# CONNECTOR_A.net
KiCad netlist of a schematic drawn in Altium Designer
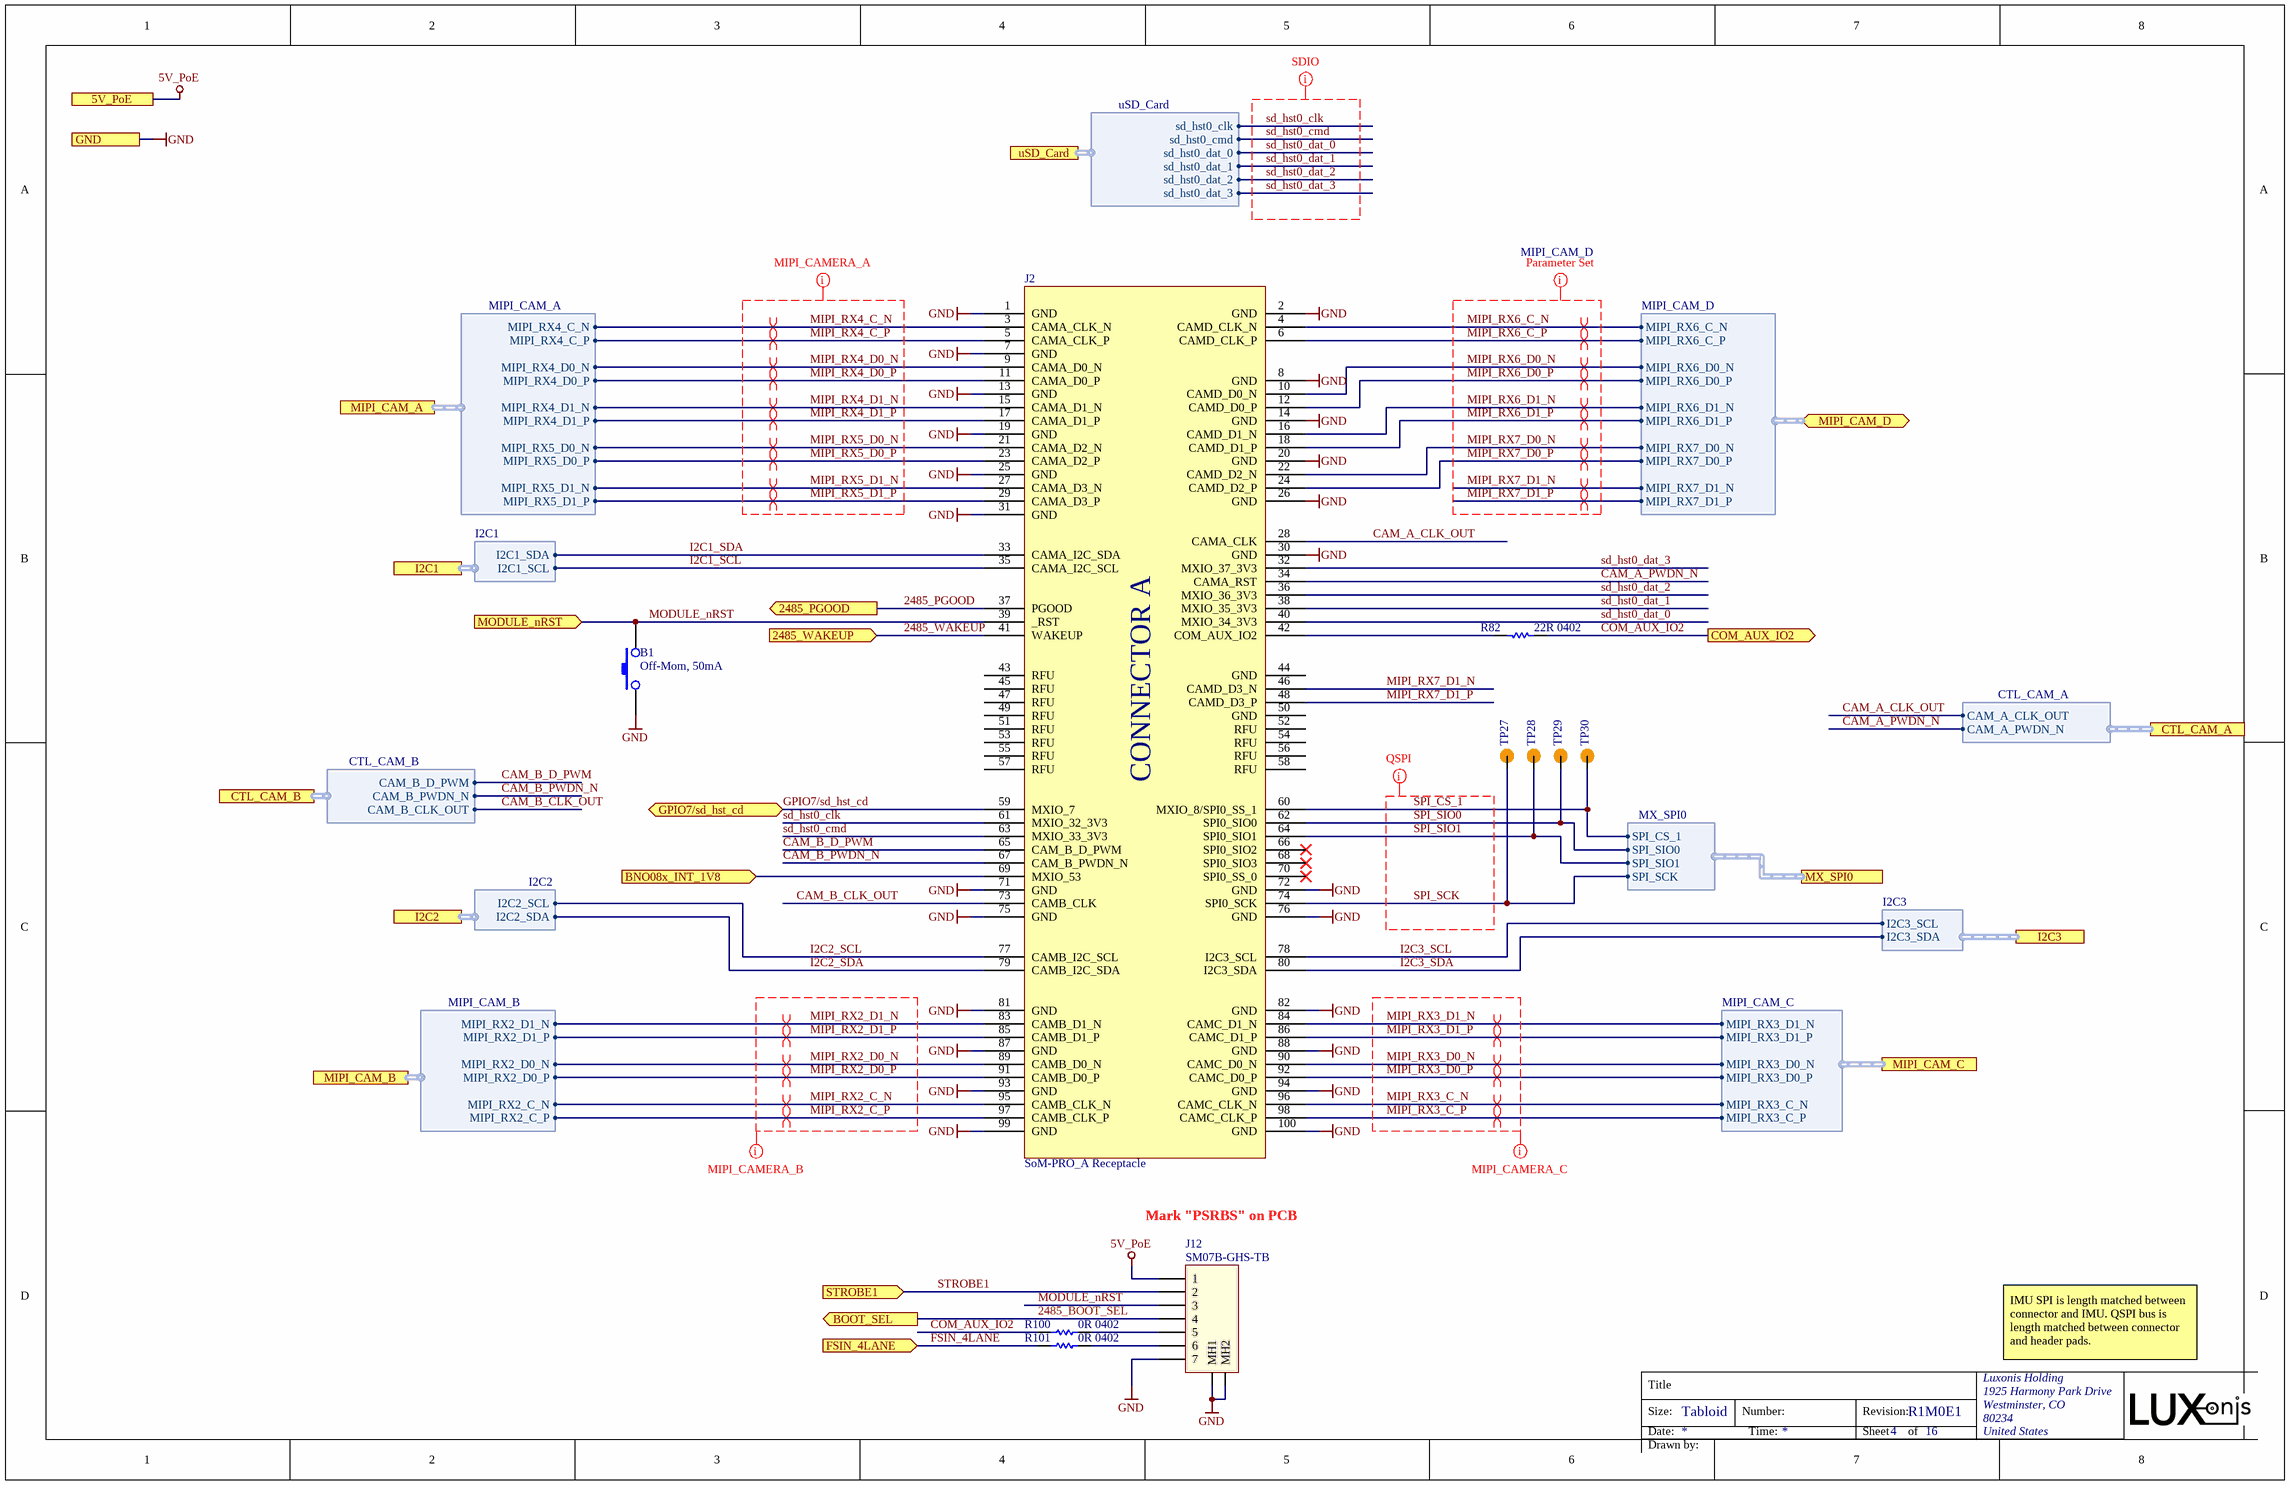
[diagram p0: CONNECTOR_A.SchDoc]

(export (version "E")
  (design (tool "Eeschema 10.0.6"))
  (components
    (comp (ref "B1")
      (value "Off-Mom, 50mA")
      (footprint "LuxonisMaster:DTSM-32N-V")
      (description "SWITCH TACTILE SMT 3.5mm * 6mm , brown 160gf")
      (libsource (lib "LuxonisMaster") (part "DTSM-32N-V"))
    )
    (comp (ref "J2")
      (value "SoM-PRO_A Receptacle")
      (footprint "LuxonisMaster:CON_A_BW2099_SoM_DF40HC-3.0-100DS-0.4V_minpad")
      (description "CONN RCPT 100POS 0.4MM SMD GOLD")
      (libsource (lib "LuxonisMaster") (part "DF40HC(3.0)-100DS-0.4V_SoM-PRO_A"))
    )
    (comp (ref "J12")
      (value "SM07B-GHS-TB")
      (footprint "SM07B-GHS-TB")
      (description "Conn Shrouded Header HDR 7 POS 1.25mm Solder RA Side Entry SMD T/R")
      (libsource (lib "DD2090_4CAM_FFC") (part "SM07B-GHS-TB(LF)(SN)"))
    )
    (comp (ref "R82")
      (value "22R 0402")
      (footprint "RES_Altium_Vault_Generic:RESC0402(1005)_L")
      (description "RES SMD 22 OHM 1% 1/16W 0402")
      (fields (field (name "TOLERANCE") "1%"))
      (libsource (lib "BW2098POE") (part "RC0402FR-0722RL"))
    )
    (comp (ref "R100")
      (value "0R 0402")
      (footprint "RES_Altium_Vault_Generic:RESC0402(1005)_L")
      (description "RES SMD 0 OHM JUMPER 1/16W 0402")
      (fields (field (name "TOLERANCE") "5%"))
      (libsource (lib "LuxonisMaster") (part "CRCW04020000Z0ED"))
    )
    (comp (ref "R101")
      (value "0R 0402")
      (footprint "RES_Altium_Vault_Generic:RESC0402(1005)_L")
      (description "RES SMD 0 OHM JUMPER 1/16W 0402")
      (fields (field (name "TOLERANCE") "5%"))
      (libsource (lib "LuxonisMaster") (part "CRCW04020000Z0ED"))
    )
    (comp (ref "TP27")
      (value "TP100_200_NS")
      (footprint "TP100_200_NS")
      (libsource (lib "LuxonisMaster") (part "TEST_POINT"))
    )
    (comp (ref "TP28")
      (value "TP100_200_NS")
      (footprint "TP100_200_NS")
      (libsource (lib "LuxonisMaster") (part "TEST_POINT"))
    )
    (comp (ref "TP29")
      (value "TP100_200_NS")
      (footprint "TP100_200_NS")
      (libsource (lib "LuxonisMaster") (part "TEST_POINT"))
    )
    (comp (ref "TP30")
      (value "TP100_200_NS")
      (footprint "TP100_200_NS")
      (libsource (lib "LuxonisMaster") (part "TEST_POINT"))
    )
  )
  (nets
    (net (code "12") (name "/2485_BOOT_SEL") (class "Default")
      (node (ref "J12") (pin "4") (pinfunction "4_4") (pintype "passive"))
    )
    (net (code "13") (name "/2485_PGOOD") (class "Default")
      (node (ref "J2") (pin "37") (pinfunction "PGOOD_37") (pintype "passive"))
    )
    (net (code "14") (name "/2485_WAKEUP") (class "Default")
      (node (ref "J2") (pin "41") (pinfunction "WAKEUP_41") (pintype "passive"))
    )
    (net (code "15") (name "/BNO08x_INT_1V8") (class "Default")
      (node (ref "J2") (pin "69") (pinfunction "MXIO_53_69") (pintype "passive"))
    )
    (net (code "16") (name "/CAM_A_CLK_OUT") (class "Default")
      (node (ref "J2") (pin "28") (pinfunction "CAMA_CLK_28") (pintype "passive"))
    )
    (net (code "17") (name "/CAM_A_PWDN_N") (class "Default")
      (node (ref "J2") (pin "34") (pinfunction "CAMA_RST_34") (pintype "passive"))
    )
    (net (code "18") (name "/CAM_B_CLK_OUT") (class "Default")
      (node (ref "J2") (pin "73") (pinfunction "CAMB_CLK_73") (pintype "passive"))
    )
    (net (code "19") (name "/CAM_B_D_PWM") (class "Default")
      (node (ref "J2") (pin "65") (pinfunction "CAM_B_D_PWM_65") (pintype "passive"))
    )
    (net (code "20") (name "/CAM_B_PWDN_N") (class "Default")
      (node (ref "J2") (pin "67") (pinfunction "CAM_B_PWDN_N_67") (pintype "passive"))
    )
    (net (code "21") (name "/COM_AUX_IO2") (class "Default")
      (node (ref "R100") (pin "1") (pinfunction "1_1") (pintype "passive"))
      (node (ref "R82") (pin "1") (pinfunction "1_1") (pintype "passive"))
    )
    (net (code "22") (name "/FSIN_4LANE") (class "Default")
      (node (ref "R101") (pin "1") (pinfunction "1_1") (pintype "passive"))
    )
    (net (code "23") (name "/GPIO7{slash}sd_hst_cd") (class "Default")
      (node (ref "J2") (pin "59") (pinfunction "MXIO_7_59") (pintype "passive"))
    )
    (net (code "24") (name "/I2C1_SCL") (class "Default")
      (node (ref "J2") (pin "35") (pinfunction "CAMA_I2C_SCL_35") (pintype "passive"))
    )
    (net (code "25") (name "/I2C1_SDA") (class "Default")
      (node (ref "J2") (pin "33") (pinfunction "CAMA_I2C_SDA_33") (pintype "passive"))
    )
    (net (code "26") (name "/I2C2_SCL") (class "Default")
      (node (ref "J2") (pin "77") (pinfunction "CAMB_I2C_SCL_77") (pintype "passive"))
    )
    (net (code "27") (name "/I2C2_SDA") (class "Default")
      (node (ref "J2") (pin "79") (pinfunction "CAMB_I2C_SDA_79") (pintype "passive"))
    )
    (net (code "28") (name "/I2C3_SCL") (class "Default")
      (node (ref "J2") (pin "78") (pinfunction "I2C3_SCL_78") (pintype "passive"))
    )
    (net (code "29") (name "/I2C3_SDA") (class "Default")
      (node (ref "J2") (pin "80") (pinfunction "I2C3_SDA_80") (pintype "passive"))
    )
    (net (code "30") (name "/MIPI_RX2_C_N") (class "Default")
      (node (ref "J2") (pin "95") (pinfunction "CAMB_CLK_N_95") (pintype "passive"))
    )
    (net (code "31") (name "/MIPI_RX2_C_P") (class "Default")
      (node (ref "J2") (pin "97") (pinfunction "CAMB_CLK_P_97") (pintype "passive"))
    )
    (net (code "32") (name "/MIPI_RX2_D0_N") (class "Default")
      (node (ref "J2") (pin "89") (pinfunction "CAMB_D0_N_89") (pintype "passive"))
    )
    (net (code "33") (name "/MIPI_RX2_D0_P") (class "Default")
      (node (ref "J2") (pin "91") (pinfunction "CAMB_D0_P_91") (pintype "passive"))
    )
    (net (code "34") (name "/MIPI_RX2_D1_N") (class "Default")
      (node (ref "J2") (pin "83") (pinfunction "CAMB_D1_N_83") (pintype "passive"))
    )
    (net (code "35") (name "/MIPI_RX2_D1_P") (class "Default")
      (node (ref "J2") (pin "85") (pinfunction "CAMB_D1_P_85") (pintype "passive"))
    )
    (net (code "36") (name "/MIPI_RX3_C_N") (class "Default")
      (node (ref "J2") (pin "96") (pinfunction "CAMC_CLK_N_96") (pintype "passive"))
    )
    (net (code "37") (name "/MIPI_RX3_C_P") (class "Default")
      (node (ref "J2") (pin "98") (pinfunction "CAMC_CLK_P_98") (pintype "passive"))
    )
    (net (code "38") (name "/MIPI_RX3_D0_N") (class "Default")
      (node (ref "J2") (pin "90") (pinfunction "CAMC_D0_N_90") (pintype "passive"))
    )
    (net (code "39") (name "/MIPI_RX3_D0_P") (class "Default")
      (node (ref "J2") (pin "92") (pinfunction "CAMC_D0_P_92") (pintype "passive"))
    )
    (net (code "40") (name "/MIPI_RX3_D1_N") (class "Default")
      (node (ref "J2") (pin "84") (pinfunction "CAMC_D1_N_84") (pintype "passive"))
    )
    (net (code "41") (name "/MIPI_RX3_D1_P") (class "Default")
      (node (ref "J2") (pin "86") (pinfunction "CAMC_D1_P_86") (pintype "passive"))
    )
    (net (code "42") (name "/MIPI_RX4_C_N") (class "Default")
      (node (ref "J2") (pin "3") (pinfunction "CAMA_CLK_N_3") (pintype "passive"))
    )
    (net (code "43") (name "/MIPI_RX4_C_P") (class "Default")
      (node (ref "J2") (pin "5") (pinfunction "CAMA_CLK_P_5") (pintype "passive"))
    )
    (net (code "44") (name "/MIPI_RX4_D0_N") (class "Default")
      (node (ref "J2") (pin "9") (pinfunction "CAMA_D0_N_9") (pintype "passive"))
    )
    (net (code "45") (name "/MIPI_RX4_D0_P") (class "Default")
      (node (ref "J2") (pin "11") (pinfunction "CAMA_D0_P_11") (pintype "passive"))
    )
    (net (code "46") (name "/MIPI_RX4_D1_N") (class "Default")
      (node (ref "J2") (pin "15") (pinfunction "CAMA_D1_N_15") (pintype "passive"))
    )
    (net (code "47") (name "/MIPI_RX4_D1_P") (class "Default")
      (node (ref "J2") (pin "17") (pinfunction "CAMA_D1_P_17") (pintype "passive"))
    )
    (net (code "48") (name "/MIPI_RX5_D0_N") (class "Default")
      (node (ref "J2") (pin "21") (pinfunction "CAMA_D2_N_21") (pintype "passive"))
    )
    (net (code "49") (name "/MIPI_RX5_D0_P") (class "Default")
      (node (ref "J2") (pin "23") (pinfunction "CAMA_D2_P_23") (pintype "passive"))
    )
    (net (code "50") (name "/MIPI_RX5_D1_N") (class "Default")
      (node (ref "J2") (pin "27") (pinfunction "CAMA_D3_N_27") (pintype "passive"))
    )
    (net (code "51") (name "/MIPI_RX5_D1_P") (class "Default")
      (node (ref "J2") (pin "29") (pinfunction "CAMA_D3_P_29") (pintype "passive"))
    )
    (net (code "52") (name "/MIPI_RX6_C_N") (class "Default")
      (node (ref "J2") (pin "4") (pinfunction "CAMD_CLK_N_4") (pintype "passive"))
    )
    (net (code "53") (name "/MIPI_RX6_C_P") (class "Default")
      (node (ref "J2") (pin "6") (pinfunction "CAMD_CLK_P_6") (pintype "passive"))
    )
    (net (code "54") (name "/MIPI_RX6_D0_N") (class "Default")
      (node (ref "J2") (pin "10") (pinfunction "CAMD_D0_N_10") (pintype "passive"))
    )
    (net (code "55") (name "/MIPI_RX6_D0_P") (class "Default")
      (node (ref "J2") (pin "12") (pinfunction "CAMD_D0_P_12") (pintype "passive"))
    )
    (net (code "56") (name "/MIPI_RX6_D1_N") (class "Default")
      (node (ref "J2") (pin "16") (pinfunction "CAMD_D1_N_16") (pintype "passive"))
    )
    (net (code "57") (name "/MIPI_RX6_D1_P") (class "Default")
      (node (ref "J2") (pin "18") (pinfunction "CAMD_D1_P_18") (pintype "passive"))
    )
    (net (code "58") (name "/MIPI_RX7_D0_N") (class "Default")
      (node (ref "J2") (pin "22") (pinfunction "CAMD_D2_N_22") (pintype "passive"))
    )
    (net (code "59") (name "/MIPI_RX7_D0_P") (class "Default")
      (node (ref "J2") (pin "24") (pinfunction "CAMD_D2_P_24") (pintype "passive"))
    )
    (net (code "60") (name "/MIPI_RX7_D1_N") (class "Default")
      (node (ref "J2") (pin "46") (pinfunction "CAMD_D3_N_46") (pintype "passive"))
    )
    (net (code "61") (name "/MIPI_RX7_D1_P") (class "Default")
      (node (ref "J2") (pin "48") (pinfunction "CAMD_D3_P_48") (pintype "passive"))
    )
    (net (code "62") (name "/MODULE_nRST") (class "Default")
      (node (ref "B1") (pin "2") (pinfunction "2_2") (pintype "passive"))
      (node (ref "J12") (pin "3") (pinfunction "3_3") (pintype "passive"))
      (node (ref "J2") (pin "39") (pinfunction "_RST_39") (pintype "passive"))
    )
    (net (code "63") (name "/SPI_CS_1") (class "Default")
      (node (ref "J2") (pin "60") (pinfunction "MXIO_8/SPI0_SS_1_60") (pintype "passive"))
      (node (ref "TP30") (pin "1") (pintype "passive"))
    )
    (net (code "64") (name "/SPI_SCK") (class "Default")
      (node (ref "J2") (pin "74") (pinfunction "SPI0_SCK_74") (pintype "passive"))
      (node (ref "TP27") (pin "1") (pintype "passive"))
    )
    (net (code "65") (name "/SPI_SIO0") (class "Default")
      (node (ref "J2") (pin "62") (pinfunction "SPI0_SIO0_62") (pintype "passive"))
      (node (ref "TP29") (pin "1") (pintype "passive"))
    )
    (net (code "66") (name "/SPI_SIO1") (class "Default")
      (node (ref "J2") (pin "64") (pinfunction "SPI0_SIO1_64") (pintype "passive"))
      (node (ref "TP28") (pin "1") (pintype "passive"))
    )
    (net (code "67") (name "/STROBE1") (class "Default")
      (node (ref "J12") (pin "2") (pinfunction "2_2") (pintype "passive"))
    )
    (net (code "68") (name "/sd_hst0_clk") (class "Default")
      (node (ref "J2") (pin "61") (pinfunction "MXIO_32_3V3_61") (pintype "passive"))
    )
    (net (code "69") (name "/sd_hst0_cmd") (class "Default")
      (node (ref "J2") (pin "63") (pinfunction "MXIO_33_3V3_63") (pintype "passive"))
    )
    (net (code "70") (name "/sd_hst0_dat_0") (class "Default")
      (node (ref "J2") (pin "40") (pinfunction "MXIO_34_3V3_40") (pintype "passive"))
    )
    (net (code "71") (name "/sd_hst0_dat_1") (class "Default")
      (node (ref "J2") (pin "38") (pinfunction "MXIO_35_3V3_38") (pintype "passive"))
    )
    (net (code "72") (name "/sd_hst0_dat_2") (class "Default")
      (node (ref "J2") (pin "36") (pinfunction "MXIO_36_3V3_36") (pintype "passive"))
    )
    (net (code "73") (name "/sd_hst0_dat_3") (class "Default")
      (node (ref "J2") (pin "32") (pinfunction "MXIO_37_3V3_32") (pintype "passive"))
    )
    (net (code "85") (name "5V_PoE") (class "Default")
      (node (ref "J12") (pin "1") (pinfunction "1_1") (pintype "passive"))
    )
    (net (code "86") (name "GND") (class "Default")
      (node (ref "B1") (pin "1") (pinfunction "1_1") (pintype "passive"))
      (node (ref "J12") (pin "7") (pinfunction "7_7") (pintype "passive"))
      (node (ref "J12") (pin "MH1") (pinfunction "MH1_MH1") (pintype "passive"))
      (node (ref "J12") (pin "MH2") (pinfunction "MH2_MH2") (pintype "passive"))
      (node (ref "J2") (pin "1") (pinfunction "GND_1") (pintype "passive"))
      (node (ref "J2") (pin "100") (pinfunction "GND_100") (pintype "passive"))
      (node (ref "J2") (pin "13") (pinfunction "GND_13") (pintype "passive"))
      (node (ref "J2") (pin "14") (pinfunction "GND_14") (pintype "passive"))
      (node (ref "J2") (pin "19") (pinfunction "GND_19") (pintype "passive"))
      (node (ref "J2") (pin "2") (pinfunction "GND_2") (pintype "passive"))
      (node (ref "J2") (pin "20") (pinfunction "GND_20") (pintype "passive"))
      (node (ref "J2") (pin "25") (pinfunction "GND_25") (pintype "passive"))
      (node (ref "J2") (pin "26") (pinfunction "GND_26") (pintype "passive"))
      (node (ref "J2") (pin "30") (pinfunction "GND_30") (pintype "passive"))
      (node (ref "J2") (pin "31") (pinfunction "GND_31") (pintype "passive"))
      (node (ref "J2") (pin "7") (pinfunction "GND_7") (pintype "passive"))
      (node (ref "J2") (pin "71") (pinfunction "GND_71") (pintype "passive"))
      (node (ref "J2") (pin "72") (pinfunction "GND_72") (pintype "passive"))
      (node (ref "J2") (pin "75") (pinfunction "GND_75") (pintype "passive"))
      (node (ref "J2") (pin "76") (pinfunction "GND_76") (pintype "passive"))
      (node (ref "J2") (pin "8") (pinfunction "GND_8") (pintype "passive"))
      (node (ref "J2") (pin "81") (pinfunction "GND_81") (pintype "passive"))
      (node (ref "J2") (pin "82") (pinfunction "GND_82") (pintype "passive"))
      (node (ref "J2") (pin "87") (pinfunction "GND_87") (pintype "passive"))
      (node (ref "J2") (pin "88") (pinfunction "GND_88") (pintype "passive"))
      (node (ref "J2") (pin "93") (pinfunction "GND_93") (pintype "passive"))
      (node (ref "J2") (pin "94") (pinfunction "GND_94") (pintype "passive"))
      (node (ref "J2") (pin "99") (pinfunction "GND_99") (pintype "passive"))
    )
    (net (code "87") (name "Net-(J2-COM_AUX_IO2)") (class "Default")
      (node (ref "J2") (pin "42") (pinfunction "COM_AUX_IO2_42") (pintype "passive"))
      (node (ref "R82") (pin "2") (pinfunction "2_2") (pintype "passive"))
    )
    (net (code "88") (name "Net-(J12-Pad5)") (class "Default")
      (node (ref "J12") (pin "5") (pinfunction "5_5") (pintype "passive"))
      (node (ref "R100") (pin "2") (pinfunction "2_2") (pintype "passive"))
    )
    (net (code "89") (name "Net-(J12-Pad6)") (class "Default")
      (node (ref "J12") (pin "6") (pinfunction "6_6") (pintype "passive"))
      (node (ref "R101") (pin "2") (pinfunction "2_2") (pintype "passive"))
    )
    (net (code "90") (name "unconnected-(J2-GND-Pad44)") (class "Default")
      (node (ref "J2") (pin "44") (pinfunction "GND_44") (pintype "passive"))
    )
    (net (code "91") (name "unconnected-(J2-GND-Pad50)") (class "Default")
      (node (ref "J2") (pin "50") (pinfunction "GND_50") (pintype "passive"))
    )
    (net (code "92") (name "unconnected-(J2-RFU-Pad43)") (class "Default")
      (node (ref "J2") (pin "43") (pinfunction "RFU_43") (pintype "passive"))
    )
    (net (code "93") (name "unconnected-(J2-RFU-Pad45)") (class "Default")
      (node (ref "J2") (pin "45") (pinfunction "RFU_45") (pintype "passive"))
    )
    (net (code "94") (name "unconnected-(J2-RFU-Pad47)") (class "Default")
      (node (ref "J2") (pin "47") (pinfunction "RFU_47") (pintype "passive"))
    )
    (net (code "95") (name "unconnected-(J2-RFU-Pad49)") (class "Default")
      (node (ref "J2") (pin "49") (pinfunction "RFU_49") (pintype "passive"))
    )
    (net (code "96") (name "unconnected-(J2-RFU-Pad51)") (class "Default")
      (node (ref "J2") (pin "51") (pinfunction "RFU_51") (pintype "passive"))
    )
    (net (code "97") (name "unconnected-(J2-RFU-Pad52)") (class "Default")
      (node (ref "J2") (pin "52") (pinfunction "RFU_52") (pintype "passive"))
    )
    (net (code "98") (name "unconnected-(J2-RFU-Pad53)") (class "Default")
      (node (ref "J2") (pin "53") (pinfunction "RFU_53") (pintype "passive"))
    )
    (net (code "99") (name "unconnected-(J2-RFU-Pad54)") (class "Default")
      (node (ref "J2") (pin "54") (pinfunction "RFU_54") (pintype "passive"))
    )
    (net (code "100") (name "unconnected-(J2-RFU-Pad55)") (class "Default")
      (node (ref "J2") (pin "55") (pinfunction "RFU_55") (pintype "passive"))
    )
    (net (code "101") (name "unconnected-(J2-RFU-Pad56)") (class "Default")
      (node (ref "J2") (pin "56") (pinfunction "RFU_56") (pintype "passive"))
    )
    (net (code "102") (name "unconnected-(J2-RFU-Pad57)") (class "Default")
      (node (ref "J2") (pin "57") (pinfunction "RFU_57") (pintype "passive"))
    )
    (net (code "103") (name "unconnected-(J2-RFU-Pad58)") (class "Default")
      (node (ref "J2") (pin "58") (pinfunction "RFU_58") (pintype "passive"))
    )
    (net (code "104") (name "unconnected-(J2-SPI0_SIO2-Pad66)") (class "Default")
      (node (ref "J2") (pin "66") (pinfunction "SPI0_SIO2_66") (pintype "passive+no_connect"))
    )
    (net (code "105") (name "unconnected-(J2-SPI0_SIO3-Pad68)") (class "Default")
      (node (ref "J2") (pin "68") (pinfunction "SPI0_SIO3_68") (pintype "passive+no_connect"))
    )
    (net (code "106") (name "unconnected-(J2-SPI0_SS_0-Pad70)") (class "Default")
      (node (ref "J2") (pin "70") (pinfunction "SPI0_SS_0_70") (pintype "passive+no_connect"))
    )
  )
)
